# OpenHealthV2.net
KiCad netlist of a schematic drawn in EAGLE
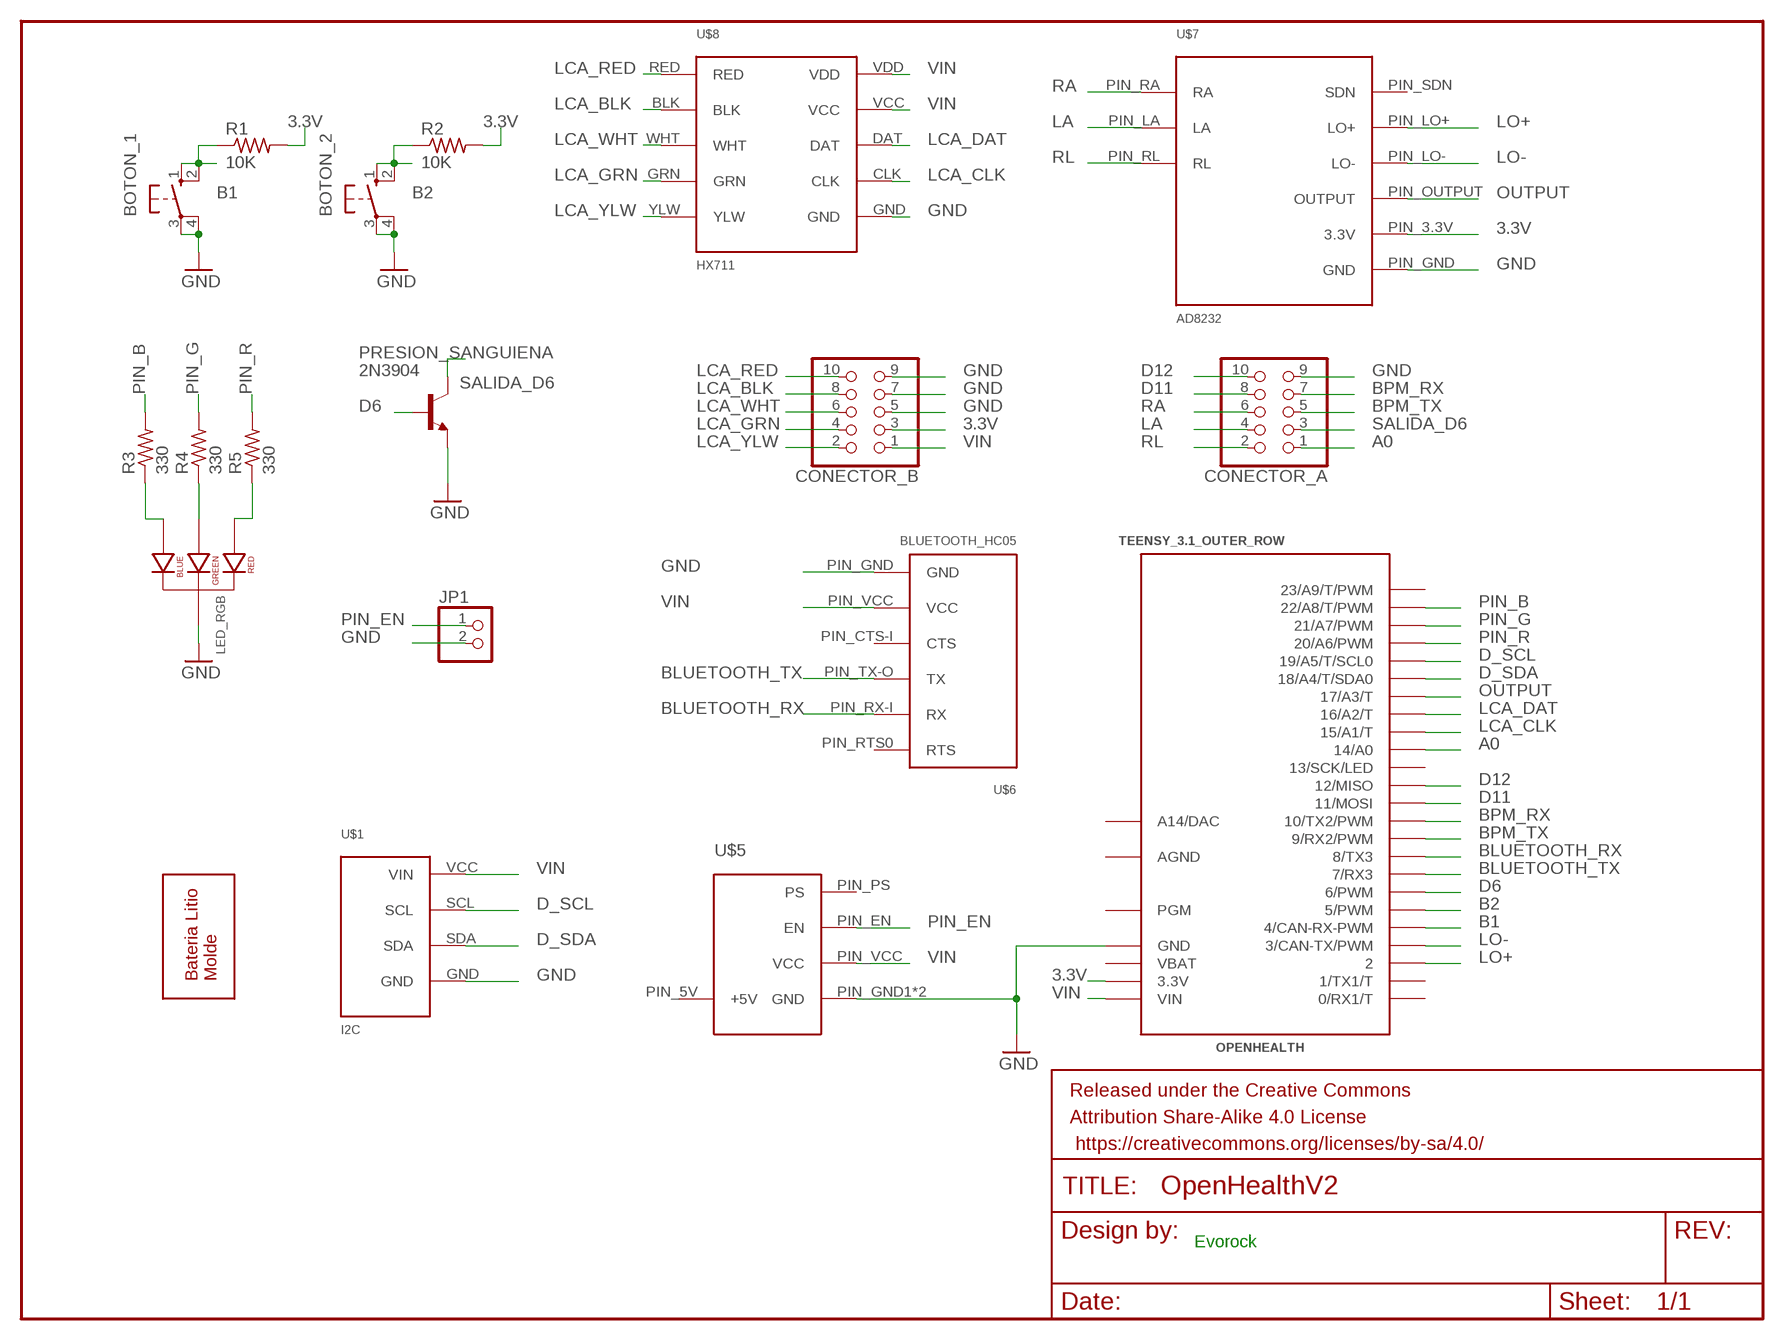
[diagram p0: schematic, sheet 1]

(export (version "E")
  (design (tool "Eeschema 10.0.6"))
  (components
    (comp (ref "BOTON_1")
      (value "10-XX")
      (footprint "eagle-import:B3F-10XX")
      (fields (field (name "MPN") "B3F-1000"))
      (libsource (lib "eagle-import") (part "10-XX"))
    )
    (comp (ref "BOTON_2")
      (value "10-XX")
      (footprint "eagle-import:B3F-10XX")
      (fields (field (name "MPN") "B3F-1000"))
      (libsource (lib "eagle-import") (part "10-XX"))
    )
    (comp (ref "CONECTOR_A")
      (value "PINHD-2X5")
      (footprint "eagle-import:2X05")
      (libsource (lib "eagle-import") (part "PINHD-2X5"))
    )
    (comp (ref "CONECTOR_B")
      (value "PINHD-2X5")
      (footprint "eagle-import:2X05")
      (libsource (lib "eagle-import") (part "PINHD-2X5"))
    )
    (comp (ref "FRAME1")
      (value "FRAME-LETTER")
      (footprint "eagle-import:CREATIVE_COMMONS")
      (libsource (lib "eagle-import") (part "FRAME-LETTER"))
    )
    (comp (ref "JP1")
      (value "PINHD-1X2")
      (footprint "eagle-import:1X02")
      (libsource (lib "eagle-import") (part "PINHD-1X2"))
    )
    (comp (ref "LED_RGB")
      (value "LED-RGB-CC-THRUCLEAR")
      (footprint "eagle-import:LED-RGB-THRU")
      (libsource (lib "eagle-import") (part "LED-RGB-CC-THRUCLEAR"))
    )
    (comp (ref "OPENHEALTH")
      (value "TEENSY_3.1_OUTER_ROW")
      (footprint "eagle-import:TEENSY3-OUTER_ROW")
      (libsource (lib "eagle-import") (part "TEENSY_3.1_OUTER_ROW"))
    )
    (comp (ref "PRESION_SANGUIENA")
      (value "2N3904")
      (footprint "eagle-import:TO92")
      (libsource (lib "eagle-import") (part "2N3904"))
    )
    (comp (ref "R1")
      (value "10K")
      (footprint "eagle-import:0204_7")
      (libsource (lib "eagle-import") (part "R-US_0204/7"))
    )
    (comp (ref "R2")
      (value "10K")
      (footprint "eagle-import:0204_7")
      (libsource (lib "eagle-import") (part "R-US_0204/7"))
    )
    (comp (ref "R3")
      (value "330")
      (footprint "eagle-import:0204_7")
      (libsource (lib "eagle-import") (part "R-US_0204/7"))
    )
    (comp (ref "R4")
      (value "330")
      (footprint "eagle-import:0204_7")
      (libsource (lib "eagle-import") (part "R-US_0204/7"))
    )
    (comp (ref "R5")
      (value "330")
      (footprint "eagle-import:0204_7")
      (libsource (lib "eagle-import") (part "R-US_0204/7"))
    )
    (comp (ref "U$1")
      (value "I2C")
      (footprint "eagle-import:I2C")
      (libsource (lib "eagle-import") (part "I2C"))
    )
    (comp (ref "U$2")
      (value "BATERRY_MOLD")
      (footprint "eagle-import:BATTERY_MOLD")
      (libsource (lib "eagle-import") (part "BATERRY_MOLD"))
    )
    (comp (ref "U$5")
      (value "LIPOWER")
      (footprint "eagle-import:LIPOWER")
      (libsource (lib "eagle-import") (part "LIPOWER"))
    )
    (comp (ref "U$6")
      (value "BLUETOOTH_HC05")
      (footprint "eagle-import:BLUETOOTH_HC05")
      (libsource (lib "eagle-import") (part "BLUETOOTH_HC05"))
    )
    (comp (ref "U$7")
      (value "AD8232")
      (footprint "eagle-import:AD8232")
      (libsource (lib "eagle-import") (part "AD8232"))
    )
    (comp (ref "U$8")
      (value "HX711")
      (footprint "eagle-import:HX711")
      (libsource (lib "eagle-import") (part "HX711"))
    )
  )
  (nets
    (net (code "1") (name "/3.3V") (class "Default")
      (node (ref "CONECTOR_B") (pin "3") (pinfunction "3_3") (pintype "passive"))
      (node (ref "OPENHEALTH") (pin "3.3V") (pinfunction "3.3V_3.3V") (pintype "power_in"))
      (node (ref "OPENHEALTH") (pin "3.3V1") (pinfunction "3.3V_3.3V1") (pintype "power_in"))
      (node (ref "R1") (pin "2") (pinfunction "2_2") (pintype "passive"))
      (node (ref "R2") (pin "2") (pinfunction "2_2") (pintype "passive"))
      (node (ref "U$7") (pin "PIN_3.3V") (pinfunction "3.3V_PIN_3.3V") (pintype "bidirectional"))
    )
    (net (code "2") (name "/A0") (class "Default")
      (node (ref "CONECTOR_A") (pin "1") (pinfunction "1_1") (pintype "passive"))
      (node (ref "OPENHEALTH") (pin "14/A0") (pinfunction "14/A0_14/A0") (pintype "bidirectional"))
    )
    (net (code "3") (name "/AGND") (class "Default")
      (node (ref "OPENHEALTH") (pin "AGND") (pinfunction "AGND_AGND") (pintype "power_in"))
    )
    (net (code "4") (name "/B1") (class "Default")
      (node (ref "BOTON_1") (pin "1") (pinfunction "S_1") (pintype "passive"))
      (node (ref "BOTON_1") (pin "2") (pinfunction "S1_2") (pintype "passive"))
      (node (ref "OPENHEALTH") (pin "4") (pinfunction "4/CAN-RX-PWM_4") (pintype "bidirectional"))
      (node (ref "R1") (pin "1") (pinfunction "1_1") (pintype "passive"))
    )
    (net (code "5") (name "/B2") (class "Default")
      (node (ref "BOTON_2") (pin "1") (pinfunction "S_1") (pintype "passive"))
      (node (ref "BOTON_2") (pin "2") (pinfunction "S1_2") (pintype "passive"))
      (node (ref "OPENHEALTH") (pin "5") (pinfunction "5/PWM_5") (pintype "bidirectional"))
      (node (ref "R2") (pin "1") (pinfunction "1_1") (pintype "passive"))
    )
    (net (code "6") (name "/BLUETOOTH_RX") (class "Default")
      (node (ref "OPENHEALTH") (pin "8") (pinfunction "8/TX3_8") (pintype "bidirectional"))
      (node (ref "U$6") (pin "PIN_RX-I") (pinfunction "RX_PIN_RX-I") (pintype "bidirectional"))
    )
    (net (code "7") (name "/BLUETOOTH_TX") (class "Default")
      (node (ref "OPENHEALTH") (pin "7") (pinfunction "7/RX3_7") (pintype "bidirectional"))
      (node (ref "U$6") (pin "PIN_TX-O") (pinfunction "TX_PIN_TX-O") (pintype "bidirectional"))
    )
    (net (code "8") (name "/BPM_RX") (class "Default")
      (node (ref "CONECTOR_A") (pin "7") (pinfunction "7_7") (pintype "passive"))
      (node (ref "OPENHEALTH") (pin "10") (pinfunction "10/TX2/PWM_10") (pintype "bidirectional"))
    )
    (net (code "9") (name "/BPM_TX") (class "Default")
      (node (ref "CONECTOR_A") (pin "5") (pinfunction "5_5") (pintype "passive"))
      (node (ref "OPENHEALTH") (pin "9") (pinfunction "9/RX2/PWM_9") (pintype "bidirectional"))
    )
    (net (code "10") (name "/D6") (class "Default")
      (node (ref "OPENHEALTH") (pin "6") (pinfunction "6/PWM_6") (pintype "bidirectional"))
      (node (ref "PRESION_SANGUIENA") (pin "2") (pinfunction "B_2") (pintype "passive"))
    )
    (net (code "11") (name "/D11") (class "Default")
      (node (ref "CONECTOR_A") (pin "8") (pinfunction "8_8") (pintype "passive"))
      (node (ref "OPENHEALTH") (pin "11") (pinfunction "11/MOSI_11") (pintype "bidirectional"))
    )
    (net (code "12") (name "/D12") (class "Default")
      (node (ref "CONECTOR_A") (pin "10") (pinfunction "10_10") (pintype "passive"))
      (node (ref "OPENHEALTH") (pin "12") (pinfunction "12/MISO_12") (pintype "bidirectional"))
    )
    (net (code "13") (name "/D_SCL") (class "Default")
      (node (ref "OPENHEALTH") (pin "19/A5") (pinfunction "19/A5/T/SCL0_19/A5") (pintype "bidirectional"))
      (node (ref "U$1") (pin "SCL") (pinfunction "SCL_SCL") (pintype "bidirectional"))
    )
    (net (code "14") (name "/D_SDA") (class "Default")
      (node (ref "OPENHEALTH") (pin "18/A4") (pinfunction "18/A4/T/SDA0_18/A4") (pintype "bidirectional"))
      (node (ref "U$1") (pin "SDA") (pinfunction "SDA_SDA") (pintype "bidirectional"))
    )
    (net (code "15") (name "/LA") (class "Default")
      (node (ref "CONECTOR_A") (pin "4") (pinfunction "4_4") (pintype "passive"))
      (node (ref "U$7") (pin "PIN_LA") (pinfunction "LA_PIN_LA") (pintype "bidirectional"))
    )
    (net (code "16") (name "/LCA_BLK") (class "Default")
      (node (ref "CONECTOR_B") (pin "8") (pinfunction "8_8") (pintype "passive"))
      (node (ref "U$8") (pin "BLK") (pinfunction "BLK_BLK") (pintype "bidirectional"))
    )
    (net (code "17") (name "/LCA_CLK") (class "Default")
      (node (ref "OPENHEALTH") (pin "15/A1") (pinfunction "15/A1/T_15/A1") (pintype "bidirectional"))
      (node (ref "U$8") (pin "CLK") (pinfunction "CLK_CLK") (pintype "bidirectional"))
    )
    (net (code "18") (name "/LCA_DAT") (class "Default")
      (node (ref "OPENHEALTH") (pin "16/A2") (pinfunction "16/A2/T_16/A2") (pintype "bidirectional"))
      (node (ref "U$8") (pin "DAT") (pinfunction "DAT_DAT") (pintype "bidirectional"))
    )
    (net (code "19") (name "/LCA_GRN") (class "Default")
      (node (ref "CONECTOR_B") (pin "4") (pinfunction "4_4") (pintype "passive"))
      (node (ref "U$8") (pin "GRN") (pinfunction "GRN_GRN") (pintype "bidirectional"))
    )
    (net (code "20") (name "/LCA_RED") (class "Default")
      (node (ref "CONECTOR_B") (pin "10") (pinfunction "10_10") (pintype "passive"))
      (node (ref "U$8") (pin "RED") (pinfunction "RED_RED") (pintype "bidirectional"))
    )
    (net (code "21") (name "/LCA_WHT") (class "Default")
      (node (ref "CONECTOR_B") (pin "6") (pinfunction "6_6") (pintype "passive"))
      (node (ref "U$8") (pin "WHT") (pinfunction "WHT_WHT") (pintype "bidirectional"))
    )
    (net (code "22") (name "/LCA_YLW") (class "Default")
      (node (ref "CONECTOR_B") (pin "2") (pinfunction "2_2") (pintype "passive"))
      (node (ref "U$8") (pin "YLW") (pinfunction "YLW_YLW") (pintype "bidirectional"))
    )
    (net (code "23") (name "/LO+") (class "Default")
      (node (ref "OPENHEALTH") (pin "2") (pinfunction "2_2") (pintype "bidirectional"))
      (node (ref "U$7") (pin "PIN_LO+") (pinfunction "LO+_PIN_LO+") (pintype "bidirectional"))
    )
    (net (code "24") (name "/LO-") (class "Default")
      (node (ref "OPENHEALTH") (pin "3") (pinfunction "3/CAN-TX/PWM_3") (pintype "bidirectional"))
      (node (ref "U$7") (pin "PIN_LO-") (pinfunction "LO-_PIN_LO-") (pintype "bidirectional"))
    )
    (net (code "25") (name "/OUTPUT") (class "Default")
      (node (ref "OPENHEALTH") (pin "17/A3") (pinfunction "17/A3/T_17/A3") (pintype "bidirectional"))
      (node (ref "U$7") (pin "PIN_OUTPUT") (pinfunction "OUTPUT_PIN_OUTPUT") (pintype "bidirectional"))
    )
    (net (code "26") (name "/PIN_B") (class "Default")
      (node (ref "OPENHEALTH") (pin "22/A8") (pinfunction "22/A8/T/PWM_22/A8") (pintype "bidirectional"))
      (node (ref "R3") (pin "2") (pinfunction "2_2") (pintype "passive"))
    )
    (net (code "27") (name "/PIN_EN") (class "Default")
      (node (ref "JP1") (pin "1") (pinfunction "1_1") (pintype "passive"))
      (node (ref "U$5") (pin "PIN_EN") (pinfunction "EN_PIN_EN") (pintype "bidirectional"))
    )
    (net (code "28") (name "/PIN_G") (class "Default")
      (node (ref "OPENHEALTH") (pin "21/A7") (pinfunction "21/A7/PWM_21/A7") (pintype "bidirectional"))
      (node (ref "R4") (pin "2") (pinfunction "2_2") (pintype "passive"))
    )
    (net (code "29") (name "/PIN_R") (class "Default")
      (node (ref "OPENHEALTH") (pin "20/A6") (pinfunction "20/A6/PWM_20/A6") (pintype "bidirectional"))
      (node (ref "R5") (pin "2") (pinfunction "2_2") (pintype "passive"))
    )
    (net (code "30") (name "/RA") (class "Default")
      (node (ref "CONECTOR_A") (pin "6") (pinfunction "6_6") (pintype "passive"))
      (node (ref "U$7") (pin "PIN_RA") (pinfunction "RA_PIN_RA") (pintype "bidirectional"))
    )
    (net (code "31") (name "/RL") (class "Default")
      (node (ref "CONECTOR_A") (pin "2") (pinfunction "2_2") (pintype "passive"))
      (node (ref "U$7") (pin "PIN_RL") (pinfunction "RL_PIN_RL") (pintype "bidirectional"))
    )
    (net (code "32") (name "/SALIDA_D6") (class "Default")
      (node (ref "CONECTOR_A") (pin "3") (pinfunction "3_3") (pintype "passive"))
      (node (ref "PRESION_SANGUIENA") (pin "1") (pinfunction "C_1") (pintype "passive"))
    )
    (net (code "33") (name "/VBAT") (class "Default")
      (node (ref "OPENHEALTH") (pin "VBAT") (pinfunction "VBAT_VBAT") (pintype "power_in"))
    )
    (net (code "34") (name "/VIN") (class "Default")
      (node (ref "CONECTOR_B") (pin "1") (pinfunction "1_1") (pintype "passive"))
      (node (ref "OPENHEALTH") (pin "VIN") (pinfunction "VIN_VIN") (pintype "power_in"))
      (node (ref "U$1") (pin "VCC") (pinfunction "VIN_VCC") (pintype "bidirectional"))
      (node (ref "U$5") (pin "PIN_VCC") (pinfunction "VCC_PIN_VCC") (pintype "bidirectional"))
      (node (ref "U$6") (pin "PIN_VCC") (pinfunction "VCC_PIN_VCC") (pintype "bidirectional"))
      (node (ref "U$8") (pin "VCC") (pinfunction "VCC_VCC") (pintype "bidirectional"))
      (node (ref "U$8") (pin "VDD") (pinfunction "VDD_VDD") (pintype "bidirectional"))
    )
    (net (code "35") (name "GND") (class "Default")
      (node (ref "BOTON_1") (pin "3") (pinfunction "P_3") (pintype "passive"))
      (node (ref "BOTON_1") (pin "4") (pinfunction "P1_4") (pintype "passive"))
      (node (ref "BOTON_2") (pin "3") (pinfunction "P_3") (pintype "passive"))
      (node (ref "BOTON_2") (pin "4") (pinfunction "P1_4") (pintype "passive"))
      (node (ref "CONECTOR_A") (pin "9") (pinfunction "9_9") (pintype "passive"))
      (node (ref "CONECTOR_B") (pin "5") (pinfunction "5_5") (pintype "passive"))
      (node (ref "CONECTOR_B") (pin "7") (pinfunction "7_7") (pintype "passive"))
      (node (ref "CONECTOR_B") (pin "9") (pinfunction "9_9") (pintype "passive"))
      (node (ref "JP1") (pin "2") (pinfunction "2_2") (pintype "passive"))
      (node (ref "LED_RGB") (pin "2") (pinfunction "CATHODE_2") (pintype "bidirectional"))
      (node (ref "OPENHEALTH") (pin "GND") (pinfunction "GND_GND") (pintype "power_in"))
      (node (ref "OPENHEALTH") (pin "GND1") (pinfunction "GND_GND1") (pintype "power_in"))
      (node (ref "PRESION_SANGUIENA") (pin "3") (pinfunction "E_3") (pintype "passive"))
      (node (ref "U$1") (pin "GND") (pinfunction "GND_GND") (pintype "bidirectional"))
      (node (ref "U$5") (pin "PIN_GND1") (pinfunction "GND_PIN_GND1") (pintype "bidirectional"))
      (node (ref "U$5") (pin "PIN_GND2") (pinfunction "GND_PIN_GND2") (pintype "bidirectional"))
      (node (ref "U$6") (pin "PIN_GND") (pinfunction "GND_PIN_GND") (pintype "bidirectional"))
      (node (ref "U$7") (pin "PIN_GND") (pinfunction "GND_PIN_GND") (pintype "bidirectional"))
      (node (ref "U$8") (pin "GND") (pinfunction "GND_GND") (pintype "bidirectional"))
    )
    (net (code "36") (name "Net-(LED_RGB-BLUE_CATHODE)") (class "Default")
      (node (ref "LED_RGB") (pin "4") (pinfunction "BLUE_CATHODE_4") (pintype "bidirectional"))
      (node (ref "R3") (pin "1") (pinfunction "1_1") (pintype "passive"))
    )
    (net (code "37") (name "Net-(LED_RGB-GREEN_CATHODE)") (class "Default")
      (node (ref "LED_RGB") (pin "3") (pinfunction "GREEN_CATHODE_3") (pintype "bidirectional"))
      (node (ref "R4") (pin "1") (pinfunction "1_1") (pintype "passive"))
    )
    (net (code "38") (name "Net-(LED_RGB-RED_CATHODE)") (class "Default")
      (node (ref "LED_RGB") (pin "1") (pinfunction "RED_CATHODE_1") (pintype "bidirectional"))
      (node (ref "R5") (pin "1") (pinfunction "1_1") (pintype "passive"))
    )
    (net (code "39") (name "unconnected-(OPENHEALTH-0{slash}RX1{slash}T-Pad0)") (class "Default")
      (node (ref "OPENHEALTH") (pin "0") (pinfunction "0/RX1/T_0") (pintype "bidirectional"))
    )
    (net (code "40") (name "unconnected-(OPENHEALTH-1{slash}TX1{slash}T-Pad1)") (class "Default")
      (node (ref "OPENHEALTH") (pin "1") (pinfunction "1/TX1/T_1") (pintype "bidirectional"))
    )
    (net (code "41") (name "unconnected-(OPENHEALTH-13{slash}SCK{slash}LED-Pad13)") (class "Default")
      (node (ref "OPENHEALTH") (pin "13") (pinfunction "13/SCK/LED_13") (pintype "bidirectional"))
    )
    (net (code "42") (name "unconnected-(OPENHEALTH-23{slash}A9{slash}T{slash}PWM-Pad23{slash}A9)") (class "Default")
      (node (ref "OPENHEALTH") (pin "23/A9") (pinfunction "23/A9/T/PWM_23/A9") (pintype "bidirectional"))
    )
    (net (code "43") (name "unconnected-(OPENHEALTH-A14{slash}DAC-PadRESET{slash}DAC)") (class "Default")
      (node (ref "OPENHEALTH") (pin "RESET/DAC") (pinfunction "A14/DAC_RESET/DAC") (pintype "bidirectional"))
    )
    (net (code "44") (name "unconnected-(OPENHEALTH-PadPGM)") (class "Default")
      (node (ref "OPENHEALTH") (pin "PGM") (pinfunction "PGM_PGM") (pintype "bidirectional"))
    )
    (net (code "45") (name "unconnected-(U$5-+5V-PadPIN_5V)") (class "Default")
      (node (ref "U$5") (pin "PIN_5V") (pinfunction "+5V_PIN_5V") (pintype "bidirectional"))
    )
    (net (code "46") (name "unconnected-(U$5-PS-PadPIN_PS)") (class "Default")
      (node (ref "U$5") (pin "PIN_PS") (pinfunction "PS_PIN_PS") (pintype "bidirectional"))
    )
    (net (code "47") (name "unconnected-(U$6-CTS-PadPIN_CTS-I)") (class "Default")
      (node (ref "U$6") (pin "PIN_CTS-I") (pinfunction "CTS_PIN_CTS-I") (pintype "bidirectional"))
    )
    (net (code "48") (name "unconnected-(U$6-RTS-PadPIN_RTS0)") (class "Default")
      (node (ref "U$6") (pin "PIN_RTS0") (pinfunction "RTS_PIN_RTS0") (pintype "bidirectional"))
    )
    (net (code "49") (name "unconnected-(U$7-SDN-PadPIN_SDN)") (class "Default")
      (node (ref "U$7") (pin "PIN_SDN") (pinfunction "SDN_PIN_SDN") (pintype "bidirectional"))
    )
  )
)
